# H01R0_Backend.net
KiCad netlist of a schematic drawn in Altium Designer
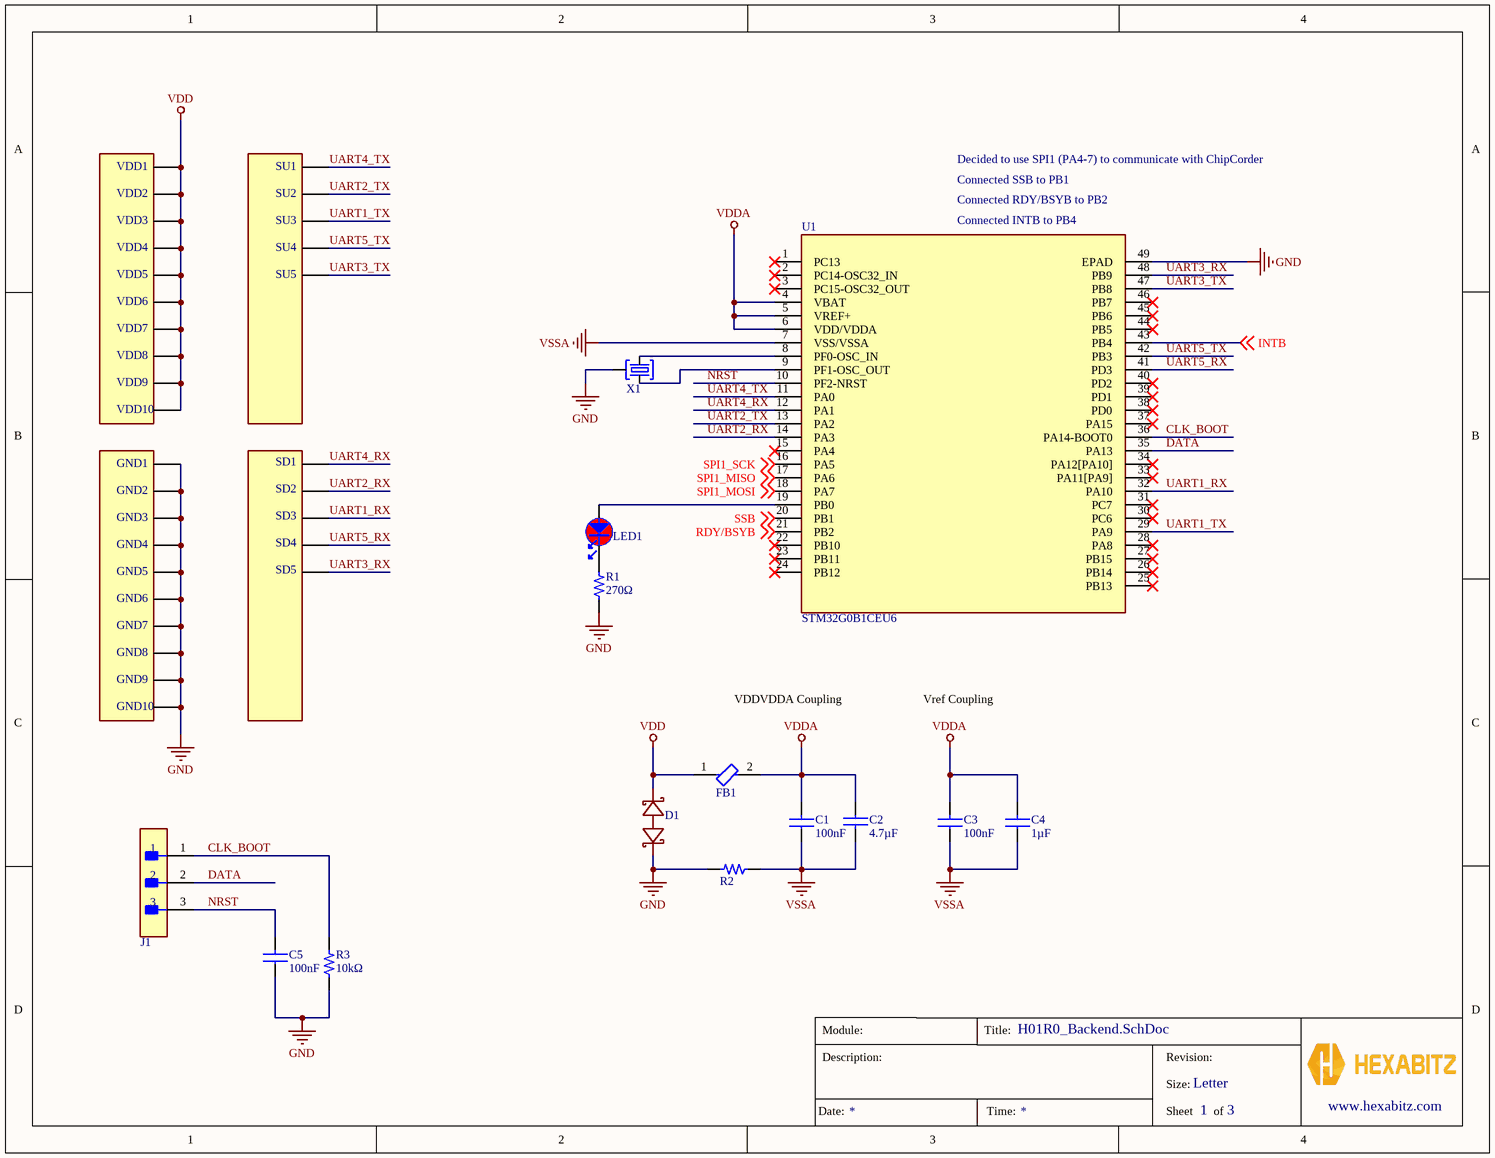
[diagram p0: H01R0_Backend.SchDoc]

(export (version "E")
  (design (tool "Eeschema 10.0.6"))
  (components
    (comp (ref "C1")
      (value "100nF")
      (footprint "C0603")
      (fields
        (field (name "MANUFACTURER") "Samsung Electro-Mechanics")
        (field (name "MANUFACTURER PART NUMBER") "CL10B104KA8NNNC")
        (field (name "TOLERANCE") "10%")
      )
      (libsource (lib "Hexabitz Altium Library") (part "generic Capacitor"))
    )
    (comp (ref "C2")
      (value "4.7µF")
      (footprint "C0805")
      (fields
        (field (name "MANUFACTURER") "Samsung Electro-Mechanics")
        (field (name "MANUFACTURER PART NUMBER") "CL21X475KAQNNNE")
        (field (name "TOLERANCE") "10%")
      )
      (libsource (lib "Hexabitz Altium Library") (part "generic Capacitor"))
    )
    (comp (ref "C3")
      (value "100nF")
      (footprint "C0603")
      (fields
        (field (name "MANUFACTURER") "Samsung Electro-Mechanics")
        (field (name "MANUFACTURER PART NUMBER") "CL10B104KA8NNNC")
        (field (name "TOLERANCE") "10%")
      )
      (libsource (lib "Hexabitz Altium Library") (part "generic Capacitor"))
    )
    (comp (ref "C4")
      (value "1µF")
      (footprint "C0805")
      (description "Ceramic Capacitor, Ceramic, 16V, 10% +Tol, 10% -Tol, X7R, 15% TC, 1uF, Surface Mount, 0805")
      (fields
        (field (name "MANUFACTURER") "Yageo Group")
        (field (name "MANUFACTURER PART NUMBER") "CC0805KKX7R7BB105")
      )
      (libsource (lib "Hexabitz Altium Library") (part "generic Capacitor"))
    )
    (comp (ref "C5")
      (value "100nF")
      (footprint "C0603")
      (fields
        (field (name "MANUFACTURER") "Samsung Electro-Mechanics")
        (field (name "MANUFACTURER PART NUMBER") "CL10B104KA8NNNC")
        (field (name "TOLERANCE") "10%")
      )
      (libsource (lib "Hexabitz Altium Library") (part "generic Capacitor"))
    )
    (comp (ref "D1")
      (value "CDSOD323-T03SC")
      (footprint "SOD2513X114N")
      (description "A 3V, 350W, bi-directional, standard capacitance, SOD323 pkg TVS Diode ¦ Bourns CDSOD323-T03SC")
      (fields (field (name "MANUFACTURER") "Bourns"))
      (libsource (lib "Hexabitz Altium Library") (part "CDSOD323-T03SC"))
    )
    (comp (ref "FB1")
      (value "MMZ1608Y300B")
      (footprint "FP-MMZ1608-0_8-MFG")
      (description "Ferrite Beads 0603 30ohms 1500mA Signal Line AEC-Q200")
      (fields
        (field (name "MANUFACTURER") "TDK")
        (field (name "MANUFACTURER PART NUMBER") "MMZ1608Y300BTD25")
      )
      (libsource (lib "Hexabitz Altium Library") (part "MMZ1608Y300B"))
    )
    (comp (ref "GND1")
      (value "HEXABIT_UART_PORT")
      (footprint "HEXABIT_POWER_PORT_D")
      (libsource (lib "hexabitz_connectors.Library") (part "HEXABIT_POWER_PORT_D"))
    )
    (comp (ref "GND2")
      (value "HEXABIT_UART_PORT")
      (footprint "HEXABIT_POWER_PORT_D")
      (libsource (lib "hexabitz_connectors.Library") (part "HEXABIT_POWER_PORT_D"))
    )
    (comp (ref "GND3")
      (value "HEXABIT_UART_PORT")
      (footprint "HEXABIT_POWER_PORT_D_300R")
      (libsource (lib "hexabitz_connectors.Library") (part "HEXABIT_POWER_PORT_D_300R"))
    )
    (comp (ref "GND4")
      (value "HEXABIT_UART_PORT")
      (footprint "HEXABIT_POWER_PORT_D")
      (libsource (lib "hexabitz_connectors.Library") (part "HEXABIT_POWER_PORT_D"))
    )
    (comp (ref "GND5")
      (value "HEXABIT_UART_PORT")
      (footprint "HEXABIT_POWER_PORT_D")
      (libsource (lib "hexabitz_connectors.Library") (part "HEXABIT_POWER_PORT_D"))
    )
    (comp (ref "GND6")
      (value "HEXABIT_UART_PORT")
      (footprint "HEXABIT_POWER_PORT_D")
      (libsource (lib "hexabitz_connectors.Library") (part "HEXABIT_POWER_PORT_D"))
    )
    (comp (ref "GND7")
      (value "HEXABIT_UART_PORT")
      (footprint "HEXABIT_POWER_PORT_D")
      (libsource (lib "hexabitz_connectors.Library") (part "HEXABIT_POWER_PORT_D"))
    )
    (comp (ref "GND8")
      (value "HEXABIT_UART_PORT")
      (footprint "HEXABIT_POWER_PORT_D_300L")
      (libsource (lib "hexabitz_connectors.Library") (part "HEXABIT_POWER_PORT_D_300L"))
    )
    (comp (ref "GND9")
      (value "HEXABIT_UART_PORT")
      (footprint "HEXABIT_POWER_PORT_D")
      (libsource (lib "hexabitz_connectors.Library") (part "HEXABIT_POWER_PORT_D"))
    )
    (comp (ref "GND10")
      (value "HEXABIT_UART_PORT")
      (footprint "HEXABIT_POWER_PORT_D")
      (libsource (lib "hexabitz_connectors.Library") (part "HEXABIT_POWER_PORT_D"))
    )
    (comp (ref "J1")
      (value "TSW-103-14-G-S")
      (footprint "FP-TSW-103-14-G-S-MFG")
      (description "CONN HEADER VERT 3POS 2.54MM")
      (libsource (lib "Altium Content Vault") (part "cd3439d6ef35ae5d9b27ec4fdd3e828"))
    )
    (comp (ref "LED1")
      (value "VLMS1300-GS08")
      (footprint "FP-6_541-5092_01-4-MFG")
      (description "LED Uni-Color Super Red 639nm 2-Pin Chip 0603(1608Metric) T/R")
      (fields (field (name "MANUFACTURER") "Vishay Semiconductors"))
      (libsource (lib "Hexabitz Altium Library") (part "VLMS1300-GS08"))
    )
    (comp (ref "R1")
      (value "270Ω")
      (footprint "R0603")
      (description "Res Thick Film 0603 270 Ohm 5% 0.1W(1/10W) ±200ppm/C Pad SMD Automotive T/R")
      (fields
        (field (name "MANUFACTURER") "Panasonic")
        (field (name "MANUFACTURER PART NUMBER") "ERJ-3GEYJ271V")
      )
      (libsource (lib "") (part "generic Resistor_1"))
    )
    (comp (ref "R2")
      (value "Manufacturer Part Number")
      (footprint "R0603")
      (libsource (lib "") (part "generic Resistor_2"))
    )
    (comp (ref "R3")
      (value "10kΩ")
      (footprint "R0603")
      (description "100mW Thick Film Resistors ±100ppm/℃ ±1% 10kΩ 0603 Chip Resistor - Surface Mount ROHS")
      (fields
        (field (name "MANUFACTURER") "Yageo Group")
        (field (name "MANUFACTURER PART NUMBER") "RC0603FR-0710KL")
      )
      (libsource (lib "Hexabitz Altium Library") (part "generic Resistor"))
    )
    (comp (ref "SD1")
      (value "HEXABIT_UART_PORT")
      (footprint "HEXABIT_UART_PORT_D")
      (libsource (lib "hexabitz_connectors.Library") (part "HEXABIT_UART_PORT_D"))
    )
    (comp (ref "SD2")
      (value "HEXABIT_UART_PORT")
      (footprint "HEXABIT_UART_PORT_D")
      (libsource (lib "hexabitz_connectors.Library") (part "HEXABIT_UART_PORT_D"))
    )
    (comp (ref "SD3")
      (value "HEXABIT_UART_PORT")
      (footprint "HEXABIT_UART_PORT_D")
      (libsource (lib "hexabitz_connectors.Library") (part "HEXABIT_UART_PORT_D"))
    )
    (comp (ref "SD4")
      (value "HEXABIT_UART_PORT")
      (footprint "HEXABIT_UART_PORT_D")
      (libsource (lib "hexabitz_connectors.Library") (part "HEXABIT_UART_PORT_D"))
    )
    (comp (ref "SD5")
      (value "HEXABIT_UART_PORT")
      (footprint "HEXABIT_UART_PORT_D")
      (libsource (lib "hexabitz_connectors.Library") (part "HEXABIT_UART_PORT_D"))
    )
    (comp (ref "SU1")
      (value "HEXABIT_UART_PORT")
      (footprint "HEXABIT_UART_PORT_U")
      (libsource (lib "hexabitz_connectors.Library") (part "HEXABIT_UART_PORT_U"))
    )
    (comp (ref "SU2")
      (value "HEXABIT_UART_PORT")
      (footprint "HEXABIT_UART_PORT_U")
      (libsource (lib "hexabitz_connectors.Library") (part "HEXABIT_UART_PORT_U"))
    )
    (comp (ref "SU3")
      (value "HEXABIT_UART_PORT")
      (footprint "HEXABIT_UART_PORT_U")
      (libsource (lib "hexabitz_connectors.Library") (part "HEXABIT_UART_PORT_U"))
    )
    (comp (ref "SU4")
      (value "HEXABIT_UART_PORT")
      (footprint "HEXABIT_UART_PORT_U")
      (libsource (lib "hexabitz_connectors.Library") (part "HEXABIT_UART_PORT_U"))
    )
    (comp (ref "SU5")
      (value "HEXABIT_UART_PORT")
      (footprint "HEXABIT_UART_PORT_U")
      (libsource (lib "hexabitz_connectors.Library") (part "HEXABIT_UART_PORT_U"))
    )
    (comp (ref "U1")
      (value "STM32G0B1CEU6")
      (footprint "QFN50P700X700X65-49N-D")
      (description "MCU 32-bit ARM Cortex M0+ RISC 512KB Flash 1.8V/2.5V/3.3V 48-Pin UFQFPN EP Tray")
      (fields
        (field (name "MANUFACTURER") "STMicroelectronics")
        (field (name "MANUFACTURER PART NUMBER") "STM32G0B1CEU6")
      )
      (libsource (lib "Hexabitz Altium Library") (part "STM32G0B1CEU6"))
    )
    (comp (ref "VDD1")
      (value "HEXABIT_UART_PORT")
      (footprint "HEXABIT_POWER_PORT_U")
      (libsource (lib "hexabitz_connectors.Library") (part "HEXABIT_POWER_PORT_U"))
    )
    (comp (ref "VDD2")
      (value "HEXABIT_UART_PORT")
      (footprint "HEXABIT_POWER_PORT_U")
      (libsource (lib "hexabitz_connectors.Library") (part "HEXABIT_POWER_PORT_U"))
    )
    (comp (ref "VDD3")
      (value "HEXABIT_UART_PORT")
      (footprint "HEXABIT_POWER_PORT_U_300R")
      (libsource (lib "hexabitz_connectors.Library") (part "HEXABIT_POWER_PORT_U_300R"))
    )
    (comp (ref "VDD4")
      (value "HEXABIT_UART_PORT")
      (footprint "HEXABIT_POWER_PORT_U")
      (libsource (lib "hexabitz_connectors.Library") (part "HEXABIT_POWER_PORT_U"))
    )
    (comp (ref "VDD5")
      (value "HEXABIT_UART_PORT")
      (footprint "HEXABIT_POWER_PORT_U")
      (libsource (lib "hexabitz_connectors.Library") (part "HEXABIT_POWER_PORT_U"))
    )
    (comp (ref "VDD6")
      (value "HEXABIT_UART_PORT")
      (footprint "HEXABIT_POWER_PORT_U")
      (libsource (lib "hexabitz_connectors.Library") (part "HEXABIT_POWER_PORT_U"))
    )
    (comp (ref "VDD7")
      (value "HEXABIT_UART_PORT")
      (footprint "HEXABIT_POWER_PORT_U")
      (libsource (lib "hexabitz_connectors.Library") (part "HEXABIT_POWER_PORT_U"))
    )
    (comp (ref "VDD8")
      (value "HEXABIT_UART_PORT")
      (footprint "HEXABIT_POWER_PORT_U_300L")
      (libsource (lib "hexabitz_connectors.Library") (part "HEXABIT_POWER_PORT_U_300L"))
    )
    (comp (ref "VDD9")
      (value "HEXABIT_UART_PORT")
      (footprint "HEXABIT_POWER_PORT_U")
      (libsource (lib "hexabitz_connectors.Library") (part "HEXABIT_POWER_PORT_U"))
    )
    (comp (ref "VDD10")
      (value "HEXABIT_UART_PORT")
      (footprint "HEXABIT_POWER_PORT_U")
      (libsource (lib "hexabitz_connectors.Library") (part "HEXABIT_POWER_PORT_U"))
    )
    (comp (ref "X1")
      (value "CSTCE8M00G52Z-R0")
      (footprint "XTALL_CSTCE8M00G52")
      (description "Ceramic Resonator 8MHz ±0.5% (Tol) ±0.2% (Stability) 10pF 40Ohm 3-Pin CSMD T/R")
      (fields (field (name "MANUFACTURER") "Murata") (field (name "TOLERANCE") "0.5%"))
      (libsource (lib "Hexabitz Altium Library") (part "CSTCE8M00G52Z-R0"))
    )
  )
  (nets
    (net (code "1") (name "/CLK_BOOT") (class "Default")
      (node (ref "J1") (pin "1") (pinfunction "1_1") (pintype "passive"))
      (node (ref "R3") (pin "1") (pinfunction "1_1") (pintype "passive"))
      (node (ref "U1") (pin "36") (pinfunction "PA14-BOOT0_36") (pintype "passive"))
    )
    (net (code "2") (name "/DATA") (class "Default")
      (node (ref "J1") (pin "2") (pinfunction "2_2") (pintype "passive"))
      (node (ref "U1") (pin "35") (pinfunction "PA13_35") (pintype "passive"))
    )
    (net (code "3") (name "/NRST") (class "Default")
      (node (ref "C5") (pin "2") (pinfunction "2_2") (pintype "passive"))
      (node (ref "J1") (pin "3") (pinfunction "3_3") (pintype "passive"))
      (node (ref "U1") (pin "10") (pinfunction "PF2-NRST_10") (pintype "passive"))
    )
    (net (code "4") (name "/UART1_RX") (class "Default")
      (node (ref "SD3") (pin "UART_D") (pinfunction "UART_D_UART_D") (pintype "passive"))
      (node (ref "U1") (pin "32") (pinfunction "PA10_32") (pintype "passive"))
    )
    (net (code "5") (name "/UART1_TX") (class "Default")
      (node (ref "SU3") (pin "UART_U") (pinfunction "UART_U_UART_U") (pintype "passive"))
      (node (ref "U1") (pin "29") (pinfunction "PA9_29") (pintype "passive"))
    )
    (net (code "6") (name "/UART2_RX") (class "Default")
      (node (ref "SD2") (pin "UART_D") (pinfunction "UART_D_UART_D") (pintype "passive"))
      (node (ref "U1") (pin "14") (pinfunction "PA3_14") (pintype "passive"))
    )
    (net (code "7") (name "/UART2_TX") (class "Default")
      (node (ref "SU2") (pin "UART_U") (pinfunction "UART_U_UART_U") (pintype "passive"))
      (node (ref "U1") (pin "13") (pinfunction "PA2_13") (pintype "passive"))
    )
    (net (code "8") (name "/UART3_RX") (class "Default")
      (node (ref "SD5") (pin "UART_D") (pinfunction "UART_D_UART_D") (pintype "passive"))
      (node (ref "U1") (pin "48") (pinfunction "PB9_48") (pintype "passive"))
    )
    (net (code "9") (name "/UART3_TX") (class "Default")
      (node (ref "SU5") (pin "UART_U") (pinfunction "UART_U_UART_U") (pintype "passive"))
      (node (ref "U1") (pin "47") (pinfunction "PB8_47") (pintype "passive"))
    )
    (net (code "10") (name "/UART4_RX") (class "Default")
      (node (ref "SD1") (pin "UART_D") (pinfunction "UART_D_UART_D") (pintype "passive"))
      (node (ref "U1") (pin "12") (pinfunction "PA1_12") (pintype "passive"))
    )
    (net (code "11") (name "/UART4_TX") (class "Default")
      (node (ref "SU1") (pin "UART_U") (pinfunction "UART_U_UART_U") (pintype "passive"))
      (node (ref "U1") (pin "11") (pinfunction "PA0_11") (pintype "passive"))
    )
    (net (code "12") (name "/UART5_RX") (class "Default")
      (node (ref "SD4") (pin "UART_D") (pinfunction "UART_D_UART_D") (pintype "passive"))
      (node (ref "U1") (pin "41") (pinfunction "PD3_41") (pintype "passive"))
    )
    (net (code "13") (name "/UART5_TX") (class "Default")
      (node (ref "SU4") (pin "UART_U") (pinfunction "UART_U_UART_U") (pintype "passive"))
      (node (ref "U1") (pin "42") (pinfunction "PB3_42") (pintype "passive"))
    )
    (net (code "14") (name "GND") (class "Default")
      (node (ref "C5") (pin "1") (pinfunction "1_1") (pintype "passive"))
      (node (ref "D1") (pin "1") (pinfunction "A_1") (pintype "passive"))
      (node (ref "GND1") (pin "Pwr_D") (pinfunction "Pwr_D_Pwr_D") (pintype "passive"))
      (node (ref "GND10") (pin "Pwr_D") (pinfunction "Pwr_D_Pwr_D") (pintype "passive"))
      (node (ref "GND2") (pin "Pwr_D") (pinfunction "Pwr_D_Pwr_D") (pintype "passive"))
      (node (ref "GND3") (pin "Pwr_D") (pinfunction "Pwr_D_Pwr_D") (pintype "passive"))
      (node (ref "GND4") (pin "Pwr_D") (pinfunction "Pwr_D_Pwr_D") (pintype "passive"))
      (node (ref "GND5") (pin "Pwr_D") (pinfunction "Pwr_D_Pwr_D") (pintype "passive"))
      (node (ref "GND6") (pin "Pwr_D") (pinfunction "Pwr_D_Pwr_D") (pintype "passive"))
      (node (ref "GND7") (pin "Pwr_D") (pinfunction "Pwr_D_Pwr_D") (pintype "passive"))
      (node (ref "GND8") (pin "Pwr_D") (pinfunction "Pwr_D_Pwr_D") (pintype "passive"))
      (node (ref "GND9") (pin "Pwr_D") (pinfunction "Pwr_D_Pwr_D") (pintype "passive"))
      (node (ref "R1") (pin "1") (pinfunction "1_1") (pintype "passive"))
      (node (ref "R2") (pin "1") (pinfunction "1_1") (pintype "passive"))
      (node (ref "R3") (pin "2") (pinfunction "2_2") (pintype "passive"))
      (node (ref "U1") (pin "49") (pinfunction "EPAD_49") (pintype "passive"))
      (node (ref "X1") (pin "P$2") (pinfunction "2_P$2") (pintype "passive"))
    )
    (net (code "15") (name "INTB") (class "Default")
      (node (ref "U1") (pin "43") (pinfunction "PB4_43") (pintype "passive"))
    )
    (net (code "16") (name "Net-(LED1-Pad1)") (class "Default")
      (node (ref "LED1") (pin "1") (pintype "passive"))
      (node (ref "R1") (pin "2") (pinfunction "2_2") (pintype "passive"))
    )
    (net (code "17") (name "Net-(U1-PB0)") (class "Default")
      (node (ref "LED1") (pin "2") (pintype "passive"))
      (node (ref "U1") (pin "19") (pinfunction "PB0_19") (pintype "passive"))
    )
    (net (code "18") (name "Net-(U1-PF0-OSC_IN)") (class "Default")
      (node (ref "U1") (pin "8") (pinfunction "PF0-OSC_IN_8") (pintype "passive"))
      (node (ref "X1") (pin "P$3") (pinfunction "3_P$3") (pintype "passive"))
    )
    (net (code "19") (name "Net-(U1-PF1-OSC_OUT)") (class "Default")
      (node (ref "U1") (pin "9") (pinfunction "PF1-OSC_OUT_9") (pintype "passive"))
      (node (ref "X1") (pin "P$1") (pinfunction "1_P$1") (pintype "passive"))
    )
    (net (code "20") (name "RDY{slash}BSYB") (class "Default")
      (node (ref "U1") (pin "21") (pinfunction "PB2_21") (pintype "passive"))
    )
    (net (code "21") (name "SPI1_MISO") (class "Default")
      (node (ref "U1") (pin "17") (pinfunction "PA6_17") (pintype "passive"))
    )
    (net (code "22") (name "SPI1_MOSI") (class "Default")
      (node (ref "U1") (pin "18") (pinfunction "PA7_18") (pintype "passive"))
    )
    (net (code "23") (name "SPI1_SCK") (class "Default")
      (node (ref "U1") (pin "16") (pinfunction "PA5_16") (pintype "passive"))
    )
    (net (code "24") (name "SSB") (class "Default")
      (node (ref "U1") (pin "20") (pinfunction "PB1_20") (pintype "passive"))
    )
    (net (code "25") (name "VDD") (class "Default")
      (node (ref "D1") (pin "2") (pinfunction "C_2") (pintype "passive"))
      (node (ref "FB1") (pin "1") (pinfunction "1_1") (pintype "passive"))
      (node (ref "VDD1") (pin "Pwr_U") (pinfunction "Pwr_U_Pwr_U") (pintype "passive"))
      (node (ref "VDD10") (pin "Pwr_U") (pinfunction "Pwr_U_Pwr_U") (pintype "passive"))
      (node (ref "VDD2") (pin "Pwr_U") (pinfunction "Pwr_U_Pwr_U") (pintype "passive"))
      (node (ref "VDD3") (pin "Pwr_U") (pinfunction "Pwr_U_Pwr_U") (pintype "passive"))
      (node (ref "VDD4") (pin "Pwr_U") (pinfunction "Pwr_U_Pwr_U") (pintype "passive"))
      (node (ref "VDD5") (pin "Pwr_U") (pinfunction "Pwr_U_Pwr_U") (pintype "passive"))
      (node (ref "VDD6") (pin "Pwr_U") (pinfunction "Pwr_U_Pwr_U") (pintype "passive"))
      (node (ref "VDD7") (pin "Pwr_U") (pinfunction "Pwr_U_Pwr_U") (pintype "passive"))
      (node (ref "VDD8") (pin "Pwr_U") (pinfunction "Pwr_U_Pwr_U") (pintype "passive"))
      (node (ref "VDD9") (pin "Pwr_U") (pinfunction "Pwr_U_Pwr_U") (pintype "passive"))
    )
    (net (code "26") (name "VDDA") (class "Default")
      (node (ref "C1") (pin "2") (pinfunction "2_2") (pintype "passive"))
      (node (ref "C2") (pin "1") (pinfunction "1_1") (pintype "passive"))
      (node (ref "C3") (pin "2") (pinfunction "2_2") (pintype "passive"))
      (node (ref "C4") (pin "2") (pinfunction "2_2") (pintype "passive"))
      (node (ref "FB1") (pin "2") (pinfunction "2_2") (pintype "passive"))
      (node (ref "U1") (pin "4") (pinfunction "VBAT_4") (pintype "passive"))
      (node (ref "U1") (pin "5") (pinfunction "VREF+_5") (pintype "passive"))
      (node (ref "U1") (pin "6") (pinfunction "VDD/VDDA_6") (pintype "passive"))
    )
    (net (code "27") (name "VSSA") (class "Default")
      (node (ref "C1") (pin "1") (pinfunction "1_1") (pintype "passive"))
      (node (ref "C2") (pin "2") (pinfunction "2_2") (pintype "passive"))
      (node (ref "C3") (pin "1") (pinfunction "1_1") (pintype "passive"))
      (node (ref "C4") (pin "1") (pinfunction "1_1") (pintype "passive"))
      (node (ref "R2") (pin "2") (pinfunction "2_2") (pintype "passive"))
      (node (ref "U1") (pin "7") (pinfunction "VSS/VSSA_7") (pintype "passive"))
    )
    (net (code "28") (name "unconnected-(U1-PA4-Pad15)") (class "Default")
      (node (ref "U1") (pin "15") (pinfunction "PA4_15") (pintype "passive+no_connect"))
    )
    (net (code "29") (name "unconnected-(U1-PA8-Pad28)") (class "Default")
      (node (ref "U1") (pin "28") (pinfunction "PA8_28") (pintype "passive+no_connect"))
    )
    (net (code "30") (name "unconnected-(U1-PA11[PA9]-Pad33)") (class "Default")
      (node (ref "U1") (pin "33") (pinfunction "PA11[PA9]_33") (pintype "passive+no_connect"))
    )
    (net (code "31") (name "unconnected-(U1-PA12[PA10]-Pad34)") (class "Default")
      (node (ref "U1") (pin "34") (pinfunction "PA12[PA10]_34") (pintype "passive+no_connect"))
    )
    (net (code "32") (name "unconnected-(U1-PA15-Pad37)") (class "Default")
      (node (ref "U1") (pin "37") (pinfunction "PA15_37") (pintype "passive+no_connect"))
    )
    (net (code "33") (name "unconnected-(U1-PB5-Pad44)") (class "Default")
      (node (ref "U1") (pin "44") (pinfunction "PB5_44") (pintype "passive+no_connect"))
    )
    (net (code "34") (name "unconnected-(U1-PB6-Pad45)") (class "Default")
      (node (ref "U1") (pin "45") (pinfunction "PB6_45") (pintype "passive+no_connect"))
    )
    (net (code "35") (name "unconnected-(U1-PB7-Pad46)") (class "Default")
      (node (ref "U1") (pin "46") (pinfunction "PB7_46") (pintype "passive+no_connect"))
    )
    (net (code "36") (name "unconnected-(U1-PB10-Pad22)") (class "Default")
      (node (ref "U1") (pin "22") (pinfunction "PB10_22") (pintype "passive+no_connect"))
    )
    (net (code "37") (name "unconnected-(U1-PB11-Pad23)") (class "Default")
      (node (ref "U1") (pin "23") (pinfunction "PB11_23") (pintype "passive+no_connect"))
    )
    (net (code "38") (name "unconnected-(U1-PB12-Pad24)") (class "Default")
      (node (ref "U1") (pin "24") (pinfunction "PB12_24") (pintype "passive+no_connect"))
    )
    (net (code "39") (name "unconnected-(U1-PB13-Pad25)") (class "Default")
      (node (ref "U1") (pin "25") (pinfunction "PB13_25") (pintype "passive+no_connect"))
    )
    (net (code "40") (name "unconnected-(U1-PB14-Pad26)") (class "Default")
      (node (ref "U1") (pin "26") (pinfunction "PB14_26") (pintype "passive+no_connect"))
    )
    (net (code "41") (name "unconnected-(U1-PB15-Pad27)") (class "Default")
      (node (ref "U1") (pin "27") (pinfunction "PB15_27") (pintype "passive+no_connect"))
    )
    (net (code "42") (name "unconnected-(U1-PC6-Pad30)") (class "Default")
      (node (ref "U1") (pin "30") (pinfunction "PC6_30") (pintype "passive+no_connect"))
    )
    (net (code "43") (name "unconnected-(U1-PC7-Pad31)") (class "Default")
      (node (ref "U1") (pin "31") (pinfunction "PC7_31") (pintype "passive+no_connect"))
    )
    (net (code "44") (name "unconnected-(U1-PC13-Pad1)") (class "Default")
      (node (ref "U1") (pin "1") (pinfunction "PC13_1") (pintype "passive+no_connect"))
    )
    (net (code "45") (name "unconnected-(U1-PC14-OSC32_IN-Pad2)") (class "Default")
      (node (ref "U1") (pin "2") (pinfunction "PC14-OSC32_IN_2") (pintype "passive+no_connect"))
    )
    (net (code "46") (name "unconnected-(U1-PC15-OSC32_OUT-Pad3)") (class "Default")
      (node (ref "U1") (pin "3") (pinfunction "PC15-OSC32_OUT_3") (pintype "passive+no_connect"))
    )
    (net (code "47") (name "unconnected-(U1-PD0-Pad38)") (class "Default")
      (node (ref "U1") (pin "38") (pinfunction "PD0_38") (pintype "passive+no_connect"))
    )
    (net (code "48") (name "unconnected-(U1-PD1-Pad39)") (class "Default")
      (node (ref "U1") (pin "39") (pinfunction "PD1_39") (pintype "passive+no_connect"))
    )
    (net (code "49") (name "unconnected-(U1-PD2-Pad40)") (class "Default")
      (node (ref "U1") (pin "40") (pinfunction "PD2_40") (pintype "passive+no_connect"))
    )
  )
)
